# STM8S103.net
KiCad netlist of a schematic drawn in Altium Designer
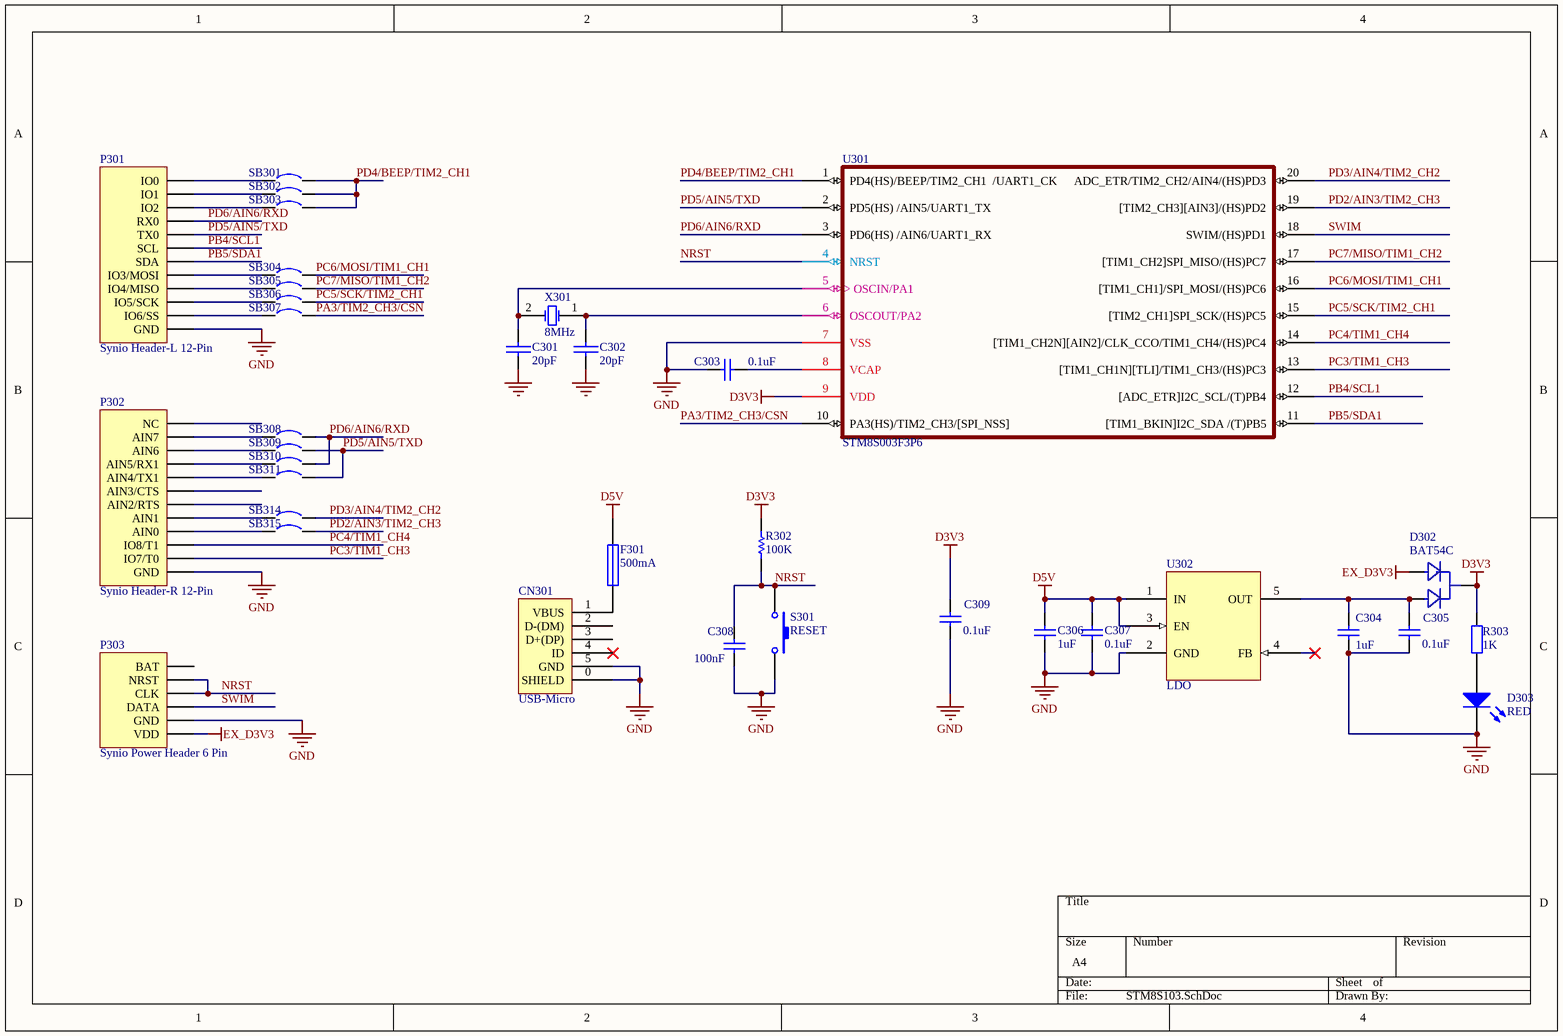
[diagram p0: STM8S103.SchDoc]

(export (version "E")
  (design (tool "Eeschema 10.0.6"))
  (components
    (comp (ref "C301")
      (value "20pF")
      (footprint "0603M")
      (description "Capacitor")
      (libsource (lib "*") (part "CAP"))
    )
    (comp (ref "C302")
      (value "20pF")
      (footprint "0603M")
      (description "Capacitor")
      (libsource (lib "*") (part "CAP"))
    )
    (comp (ref "C303")
      (value "0.1uF")
      (footprint "C0603L")
      (description "Capacitor")
      (libsource (lib "Misc") (part "Cap"))
    )
    (comp (ref "C304")
      (value "1uF")
      (footprint "0603M")
      (description "Capacitor")
      (libsource (lib "Studio") (part "Cap"))
    )
    (comp (ref "C305")
      (value "0.1uF")
      (footprint "0603M")
      (description "Capacitor")
      (libsource (lib "Studio") (part "Cap"))
    )
    (comp (ref "C306")
      (value "1uF")
      (footprint "C0603L")
      (description "Capacitor")
      (fields (field (name "Comment") "Cap") (field (name "PUBLISHER") "Altium Limited"))
      (libsource (lib "Miscellaneous Devices") (part "Cap"))
    )
    (comp (ref "C307")
      (value "0.1uF")
      (footprint "C0603L")
      (description "Capacitor")
      (fields (field (name "Comment") "Cap") (field (name "PUBLISHER") "Altium Limited"))
      (libsource (lib "Miscellaneous Devices") (part "Cap"))
    )
    (comp (ref "C308")
      (value "100nF")
      (footprint "0603M")
      (description "Capacitor")
      (fields (field (name "PUBLISHER") "Altium Limited"))
      (libsource (lib "Miscellaneous Devices") (part "CAP"))
    )
    (comp (ref "C309")
      (value "0.1uF")
      (footprint "0603M")
      (description "Capacitor")
      (libsource (lib "Studio") (part "Cap"))
    )
    (comp (ref "CN301")
      (value "USB-Micro")
      (footprint "USB-MICRO-Female-Lite")
      (libsource (lib "Connector") (part "USB-Micro"))
    )
    (comp (ref "D302")
      (value "BAT54C")
      (footprint "BAT54C")
      (description "DOUBLE SHOTTKEY DIODES")
      (libsource (lib "Misc") (part "BAT54C"))
    )
    (comp (ref "D303")
      (value "RED")
      (footprint "0603pn")
      (description "Typical INFRARED GaAs LED")
      (fields (field (name "PUBLISHER") "Altium Limited"))
      (libsource (lib "Miscellaneous Devices") (part "LED0"))
    )
    (comp (ref "F301")
      (value "500mA")
      (footprint "0805")
      (description "Fuse")
      (fields (field (name "PUBLISHER") "Altium Limited"))
      (libsource (lib "Studio") (part "Fuse 1"))
    )
    (comp (ref "P301")
      (value "Synio Header-L 12-Pin")
      (footprint "HDR1X12")
      (description "Synio Header-L, 12-Pin")
      (fields (field (name "PUBLISHER") "Altium Limited"))
      (libsource (lib "Connector") (part "Synio Header-L 12-Pin"))
    )
    (comp (ref "P302")
      (value "Synio Header-R 12-Pin")
      (footprint "HDR1X12")
      (description "Synio Header-R, 12-Pin")
      (fields (field (name "PUBLISHER") "Altium Limited"))
      (libsource (lib "Connector") (part "Synio Header-R 12-Pin"))
    )
    (comp (ref "P303")
      (value "Synio Power Header 6 Pin")
      (footprint "HDR1X6/2.54MM")
      (libsource (lib "Connector") (part "Synio Power Header 6 Pin"))
    )
    (comp (ref "R302")
      (value "100K")
      (footprint "0603M")
      (description "Resistor")
      (fields (field (name "PUBLISHER") "Altium Limited"))
      (libsource (lib "Miscellaneous Devices") (part "res1"))
    )
    (comp (ref "R303")
      (value "1K")
      (footprint "0603M")
      (description "Resistor")
      (fields (field (name "PUBLISHER") "Altium Limited"))
      (libsource (lib "Miscellaneous Devices") (part "Res2"))
    )
    (comp (ref "S301")
      (value "RESET")
      (footprint "KEY-2x4-SMD")
      (description "Switch")
      (fields (field (name "PUBLISHER") "Altium Limited"))
      (libsource (lib "Miscellaneous Devices") (part "SW-PB"))
    )
    (comp (ref "SB301")
      (value "Circuit Breaker")
      (footprint "JP2_SMD")
      (fields (field (name "PUBLISHER") "Altium Limited"))
      (libsource (lib "Misc") (part "Circuit Breaker"))
    )
    (comp (ref "SB302")
      (value "Circuit Breaker")
      (footprint "JP2_SMD")
      (fields (field (name "PUBLISHER") "Altium Limited"))
      (libsource (lib "Misc") (part "Circuit Breaker"))
    )
    (comp (ref "SB303")
      (value "Circuit Breaker")
      (footprint "JP2_SMD")
      (fields (field (name "PUBLISHER") "Altium Limited"))
      (libsource (lib "Misc") (part "Circuit Breaker"))
    )
    (comp (ref "SB304")
      (value "Circuit Breaker")
      (footprint "JP2_SMD")
      (fields (field (name "PUBLISHER") "Altium Limited"))
      (libsource (lib "Misc") (part "Circuit Breaker"))
    )
    (comp (ref "SB305")
      (value "Circuit Breaker")
      (footprint "JP2_SMD")
      (fields (field (name "PUBLISHER") "Altium Limited"))
      (libsource (lib "Misc") (part "Circuit Breaker"))
    )
    (comp (ref "SB306")
      (value "Circuit Breaker")
      (footprint "JP2_SMD")
      (fields (field (name "PUBLISHER") "Altium Limited"))
      (libsource (lib "Misc") (part "Circuit Breaker"))
    )
    (comp (ref "SB307")
      (value "Circuit Breaker")
      (footprint "JP2_SMD")
      (fields (field (name "PUBLISHER") "Altium Limited"))
      (libsource (lib "Misc") (part "Circuit Breaker"))
    )
    (comp (ref "SB308")
      (value "Circuit Breaker")
      (footprint "JP2_SMD")
      (fields (field (name "PUBLISHER") "Altium Limited"))
      (libsource (lib "Misc") (part "Circuit Breaker"))
    )
    (comp (ref "SB309")
      (value "Circuit Breaker")
      (footprint "JP2_SMD")
      (fields (field (name "PUBLISHER") "Altium Limited"))
      (libsource (lib "Misc") (part "Circuit Breaker"))
    )
    (comp (ref "SB310")
      (value "Circuit Breaker")
      (footprint "JP2_SMD")
      (fields (field (name "PUBLISHER") "Altium Limited"))
      (libsource (lib "Misc") (part "Circuit Breaker"))
    )
    (comp (ref "SB311")
      (value "Circuit Breaker")
      (footprint "JP2_SMD")
      (fields (field (name "PUBLISHER") "Altium Limited"))
      (libsource (lib "Misc") (part "Circuit Breaker"))
    )
    (comp (ref "SB314")
      (value "Circuit Breaker")
      (footprint "JP2_SMD")
      (fields (field (name "PUBLISHER") "Altium Limited"))
      (libsource (lib "Misc") (part "Circuit Breaker"))
    )
    (comp (ref "SB315")
      (value "Circuit Breaker")
      (footprint "JP2_SMD")
      (fields (field (name "PUBLISHER") "Altium Limited"))
      (libsource (lib "Misc") (part "Circuit Breaker"))
    )
    (comp (ref "U301")
      (value "STM8S003F3P6")
      (footprint "TSSOP20")
      (description "ST 8-bit  Microcontroller")
      (libsource (lib "Microcontroller Unit") (part "STM8S103F2P6"))
    )
    (comp (ref "U302")
      (value "LDO")
      (footprint "SOT23-5")
      (description "General LDO SOT23-5")
      (libsource (lib "Power") (part "LDO-SOT23-5"))
    )
    (comp (ref "X301")
      (value "8MHz")
      (footprint "XTAL_49S")
      (description "Crystal Oscillator")
      (fields (field (name "PUBLISHER") "Altium Limited"))
      (libsource (lib "MCD_TOOLS") (part "XTAL"))
    )
  )
  (nets
    (net (code "1") (name "/NRST") (class "Default")
      (node (ref "C308") (pin "2") (pinfunction "2_2") (pintype "passive"))
      (node (ref "P303") (pin "4") (pinfunction "CLK_4") (pintype "passive"))
      (node (ref "P303") (pin "5") (pinfunction "NRST_5") (pintype "passive"))
      (node (ref "R302") (pin "1") (pinfunction "1_1") (pintype "passive"))
      (node (ref "S301") (pin "2") (pinfunction "2_2") (pintype "passive"))
      (node (ref "U301") (pin "4") (pinfunction "NRST_4") (pintype "bidirectional"))
    )
    (net (code "2") (name "/PA3{slash}TIM2_CH3{slash}CSN") (class "Default")
      (node (ref "SB307") (pin "2") (pinfunction "2_2") (pintype "passive"))
      (node (ref "U301") (pin "10") (pinfunction "PA3(HS)/TIM2_CH3/[SPI_NSS]_10") (pintype "bidirectional"))
    )
    (net (code "3") (name "/PB4{slash}SCL1") (class "Default")
      (node (ref "P301") (pin "7") (pinfunction "SCL_7") (pintype "passive"))
      (node (ref "U301") (pin "12") (pinfunction "[ADC_ETR]I2C_SCL/(T)PB4_12") (pintype "bidirectional"))
    )
    (net (code "4") (name "/PB5{slash}SDA1") (class "Default")
      (node (ref "P301") (pin "6") (pinfunction "SDA_6") (pintype "passive"))
      (node (ref "U301") (pin "11") (pinfunction "[TIM1_BKIN]I2C_SDA_/(T)PB5_11") (pintype "bidirectional"))
    )
    (net (code "5") (name "/PC3{slash}TIM1_CH3") (class "Default")
      (node (ref "P302") (pin "2") (pinfunction "IO7/T0_2") (pintype "passive"))
      (node (ref "U301") (pin "13") (pinfunction "[TIM1_CH1N][TLI]/TIM1_CH3/(HS)PC3_13") (pintype "bidirectional"))
    )
    (net (code "6") (name "/PC4{slash}TIM1_CH4") (class "Default")
      (node (ref "P302") (pin "3") (pinfunction "IO8/T1_3") (pintype "passive"))
      (node (ref "U301") (pin "14") (pinfunction "[TIM1_CH2N][AIN2]/CLK_CCO/TIM1_CH4/(HS)PC4_14") (pintype "bidirectional"))
    )
    (net (code "7") (name "/PC5{slash}SCK{slash}TIM2_CH1") (class "Default")
      (node (ref "SB306") (pin "2") (pinfunction "2_2") (pintype "passive"))
      (node (ref "U301") (pin "15") (pinfunction "[TIM2_CH1]SPI_SCK/(HS)PC5_15") (pintype "bidirectional"))
    )
    (net (code "8") (name "/PC6{slash}MOSI{slash}TIM1_CH1") (class "Default")
      (node (ref "SB304") (pin "2") (pinfunction "2_2") (pintype "passive"))
      (node (ref "U301") (pin "16") (pinfunction "[TIM1_CH1]/SPI_MOSI/(HS)PC6_16") (pintype "bidirectional"))
    )
    (net (code "9") (name "/PC7{slash}MISO{slash}TIM1_CH2") (class "Default")
      (node (ref "SB305") (pin "2") (pinfunction "2_2") (pintype "passive"))
      (node (ref "U301") (pin "17") (pinfunction "[TIM1_CH2]SPI_MISO/(HS)PC7_17") (pintype "bidirectional"))
    )
    (net (code "10") (name "/PD2{slash}AIN3{slash}TIM2_CH3") (class "Default")
      (node (ref "SB315") (pin "2") (pinfunction "2_2") (pintype "passive"))
      (node (ref "U301") (pin "19") (pinfunction "[TIM2_CH3][AIN3]/(HS)PD2_19") (pintype "bidirectional"))
    )
    (net (code "11") (name "/PD3{slash}AIN4{slash}TIM2_CH2") (class "Default")
      (node (ref "SB314") (pin "2") (pinfunction "2_2") (pintype "passive"))
      (node (ref "U301") (pin "20") (pinfunction "ADC_ETR/TIM2_CH2/AIN4/(HS)PD3_20") (pintype "bidirectional"))
    )
    (net (code "12") (name "/PD4{slash}BEEP{slash}TIM2_CH1") (class "Default")
      (node (ref "SB301") (pin "2") (pinfunction "2_2") (pintype "passive"))
      (node (ref "SB302") (pin "2") (pinfunction "2_2") (pintype "passive"))
      (node (ref "SB303") (pin "2") (pinfunction "2_2") (pintype "passive"))
      (node (ref "U301") (pin "1") (pinfunction "PD4(HS)/BEEP/TIM2_CH1__/UART1_CK_1") (pintype "bidirectional"))
    )
    (net (code "13") (name "/PD5{slash}AIN5{slash}TXD") (class "Default")
      (node (ref "P301") (pin "8") (pinfunction "TX0_8") (pintype "passive"))
      (node (ref "SB309") (pin "2") (pinfunction "2_2") (pintype "passive"))
      (node (ref "SB311") (pin "2") (pinfunction "2_2") (pintype "passive"))
      (node (ref "U301") (pin "2") (pinfunction "PD5(HS)_/AIN5/UART1_TX_2") (pintype "bidirectional"))
    )
    (net (code "14") (name "/PD6{slash}AIN6{slash}RXD") (class "Default")
      (node (ref "P301") (pin "9") (pinfunction "RX0_9") (pintype "passive"))
      (node (ref "SB308") (pin "2") (pinfunction "2_2") (pintype "passive"))
      (node (ref "SB310") (pin "2") (pinfunction "2_2") (pintype "passive"))
      (node (ref "U301") (pin "3") (pinfunction "PD6(HS)_/AIN6/UART1_RX_3") (pintype "bidirectional"))
    )
    (net (code "15") (name "/SWIM") (class "Default")
      (node (ref "P303") (pin "3") (pinfunction "DATA_3") (pintype "passive"))
      (node (ref "U301") (pin "18") (pinfunction "SWIM/(HS)PD1_18") (pintype "bidirectional"))
    )
    (net (code "16") (name "D3V3") (class "Default")
      (node (ref "C309") (pin "2") (pinfunction "2_2") (pintype "passive"))
      (node (ref "D302") (pin "3") (pinfunction "3_3") (pintype "passive"))
      (node (ref "R302") (pin "2") (pinfunction "2_2") (pintype "passive"))
      (node (ref "R303") (pin "2") (pinfunction "2_2") (pintype "passive"))
      (node (ref "U301") (pin "9") (pinfunction "VDD_9") (pintype "power_in"))
    )
    (net (code "17") (name "D5V") (class "Default")
      (node (ref "C306") (pin "2") (pinfunction "2_2") (pintype "passive"))
      (node (ref "C307") (pin "2") (pinfunction "2_2") (pintype "passive"))
      (node (ref "F301") (pin "1") (pinfunction "1_1") (pintype "passive"))
      (node (ref "U302") (pin "1") (pinfunction "IN_1") (pintype "power_in"))
      (node (ref "U302") (pin "3") (pinfunction "EN_3") (pintype "input"))
    )
    (net (code "18") (name "EX_D3V3") (class "Default")
      (node (ref "D302") (pin "1") (pintype "passive"))
      (node (ref "P303") (pin "1") (pinfunction "VDD_1") (pintype "passive"))
    )
    (net (code "19") (name "GND") (class "Default")
      (node (ref "C301") (pin "2") (pinfunction "2_2") (pintype "passive"))
      (node (ref "C302") (pin "2") (pinfunction "2_2") (pintype "passive"))
      (node (ref "C303") (pin "2") (pinfunction "2_2") (pintype "passive"))
      (node (ref "C304") (pin "1") (pinfunction "1_1") (pintype "passive"))
      (node (ref "C305") (pin "1") (pinfunction "1_1") (pintype "passive"))
      (node (ref "C306") (pin "1") (pinfunction "1_1") (pintype "passive"))
      (node (ref "C307") (pin "1") (pinfunction "1_1") (pintype "passive"))
      (node (ref "C308") (pin "1") (pinfunction "1_1") (pintype "passive"))
      (node (ref "C309") (pin "1") (pinfunction "1_1") (pintype "passive"))
      (node (ref "CN301") (pin "0") (pinfunction "SHIELD_0") (pintype "passive"))
      (node (ref "CN301") (pin "5") (pinfunction "GND_5") (pintype "passive"))
      (node (ref "D303") (pin "2") (pinfunction "K_2") (pintype "passive"))
      (node (ref "P301") (pin "1") (pinfunction "GND_1") (pintype "passive"))
      (node (ref "P302") (pin "1") (pinfunction "GND_1") (pintype "passive"))
      (node (ref "P303") (pin "2") (pinfunction "GND_2") (pintype "passive"))
      (node (ref "S301") (pin "1") (pinfunction "1_1") (pintype "passive"))
      (node (ref "U301") (pin "7") (pinfunction "VSS_7") (pintype "power_in"))
      (node (ref "U302") (pin "2") (pinfunction "GND_2") (pintype "power_in"))
    )
    (net (code "20") (name "Net-(CN301-VBUS)") (class "Default")
      (node (ref "CN301") (pin "1") (pinfunction "VBUS_1") (pintype "passive"))
      (node (ref "F301") (pin "2") (pinfunction "2_2") (pintype "passive"))
    )
    (net (code "21") (name "Net-(D303-A)") (class "Default")
      (node (ref "D303") (pin "1") (pinfunction "A_1") (pintype "passive"))
      (node (ref "R303") (pin "1") (pinfunction "1_1") (pintype "passive"))
    )
    (net (code "22") (name "Net-(P301-IO0)") (class "Default")
      (node (ref "P301") (pin "12") (pinfunction "IO0_12") (pintype "passive"))
      (node (ref "SB301") (pin "1") (pinfunction "1_1") (pintype "passive"))
    )
    (net (code "23") (name "Net-(P301-IO1)") (class "Default")
      (node (ref "P301") (pin "11") (pinfunction "IO1_11") (pintype "passive"))
      (node (ref "SB302") (pin "1") (pinfunction "1_1") (pintype "passive"))
    )
    (net (code "24") (name "Net-(P301-IO2)") (class "Default")
      (node (ref "P301") (pin "10") (pinfunction "IO2_10") (pintype "passive"))
      (node (ref "SB303") (pin "1") (pinfunction "1_1") (pintype "passive"))
    )
    (net (code "25") (name "Net-(P301-IO3{slash}MOSI)") (class "Default")
      (node (ref "P301") (pin "5") (pinfunction "IO3/MOSI_5") (pintype "passive"))
      (node (ref "SB304") (pin "1") (pinfunction "1_1") (pintype "passive"))
    )
    (net (code "26") (name "Net-(P301-IO4{slash}MISO)") (class "Default")
      (node (ref "P301") (pin "4") (pinfunction "IO4/MISO_4") (pintype "passive"))
      (node (ref "SB305") (pin "1") (pinfunction "1_1") (pintype "passive"))
    )
    (net (code "27") (name "Net-(P301-IO5{slash}SCK)") (class "Default")
      (node (ref "P301") (pin "3") (pinfunction "IO5/SCK_3") (pintype "passive"))
      (node (ref "SB306") (pin "1") (pinfunction "1_1") (pintype "passive"))
    )
    (net (code "28") (name "Net-(P301-IO6{slash}SS)") (class "Default")
      (node (ref "P301") (pin "2") (pinfunction "IO6/SS_2") (pintype "passive"))
      (node (ref "SB307") (pin "1") (pinfunction "1_1") (pintype "passive"))
    )
    (net (code "29") (name "Net-(P302-AIN0)") (class "Default")
      (node (ref "P302") (pin "4") (pinfunction "AIN0_4") (pintype "passive"))
      (node (ref "SB315") (pin "1") (pinfunction "1_1") (pintype "passive"))
    )
    (net (code "30") (name "Net-(P302-AIN1)") (class "Default")
      (node (ref "P302") (pin "5") (pinfunction "AIN1_5") (pintype "passive"))
      (node (ref "SB314") (pin "1") (pinfunction "1_1") (pintype "passive"))
    )
    (net (code "31") (name "Net-(P302-AIN4{slash}TX1)") (class "Default")
      (node (ref "P302") (pin "8") (pinfunction "AIN4/TX1_8") (pintype "passive"))
      (node (ref "SB311") (pin "1") (pinfunction "1_1") (pintype "passive"))
    )
    (net (code "32") (name "Net-(P302-AIN5{slash}RX1)") (class "Default")
      (node (ref "P302") (pin "9") (pinfunction "AIN5/RX1_9") (pintype "passive"))
      (node (ref "SB310") (pin "1") (pinfunction "1_1") (pintype "passive"))
    )
    (net (code "33") (name "Net-(P302-AIN6)") (class "Default")
      (node (ref "P302") (pin "10") (pinfunction "AIN6_10") (pintype "passive"))
      (node (ref "SB309") (pin "1") (pinfunction "1_1") (pintype "passive"))
    )
    (net (code "34") (name "Net-(P302-AIN7)") (class "Default")
      (node (ref "P302") (pin "11") (pinfunction "AIN7_11") (pintype "passive"))
      (node (ref "SB308") (pin "1") (pinfunction "1_1") (pintype "passive"))
    )
    (net (code "35") (name "Net-(U301-OSCIN{slash}PA1)") (class "Default")
      (node (ref "C301") (pin "1") (pinfunction "1_1") (pintype "passive"))
      (node (ref "U301") (pin "5") (pinfunction "OSCIN/PA1_5") (pintype "bidirectional"))
      (node (ref "X301") (pin "2") (pinfunction "OSC2_2") (pintype "passive"))
    )
    (net (code "36") (name "Net-(U301-OSCOUT{slash}PA2)") (class "Default")
      (node (ref "C302") (pin "1") (pinfunction "1_1") (pintype "passive"))
      (node (ref "U301") (pin "6") (pinfunction "OSCOUT/PA2_6") (pintype "bidirectional"))
      (node (ref "X301") (pin "1") (pinfunction "OSC1_1") (pintype "passive"))
    )
    (net (code "37") (name "Net-(U301-VCAP)") (class "Default")
      (node (ref "C303") (pin "1") (pinfunction "1_1") (pintype "passive"))
      (node (ref "U301") (pin "8") (pinfunction "VCAP_8") (pintype "power_in"))
    )
    (net (code "38") (name "Net-(U302-OUT)") (class "Default")
      (node (ref "C304") (pin "2") (pinfunction "2_2") (pintype "passive"))
      (node (ref "C305") (pin "2") (pinfunction "2_2") (pintype "passive"))
      (node (ref "D302") (pin "2") (pintype "passive"))
      (node (ref "U302") (pin "5") (pinfunction "OUT_5") (pintype "power_in"))
    )
    (net (code "39") (name "unconnected-(CN301-D+(DP)-Pad3)") (class "Default")
      (node (ref "CN301") (pin "3") (pinfunction "D+(DP)_3") (pintype "passive"))
    )
    (net (code "40") (name "unconnected-(CN301-D-(DM)-Pad2)") (class "Default")
      (node (ref "CN301") (pin "2") (pinfunction "D-(DM)_2") (pintype "passive"))
    )
    (net (code "41") (name "unconnected-(CN301-ID-Pad4)") (class "Default")
      (node (ref "CN301") (pin "4") (pinfunction "ID_4") (pintype "passive+no_connect"))
    )
    (net (code "42") (name "unconnected-(P302-AIN2{slash}RTS-Pad6)") (class "Default")
      (node (ref "P302") (pin "6") (pinfunction "AIN2/RTS_6") (pintype "passive"))
    )
    (net (code "43") (name "unconnected-(P302-AIN3{slash}CTS-Pad7)") (class "Default")
      (node (ref "P302") (pin "7") (pinfunction "AIN3/CTS_7") (pintype "passive"))
    )
    (net (code "44") (name "unconnected-(P302-NC-Pad12)") (class "Default")
      (node (ref "P302") (pin "12") (pinfunction "NC_12") (pintype "passive"))
    )
    (net (code "45") (name "unconnected-(P303-BAT-Pad6)") (class "Default")
      (node (ref "P303") (pin "6") (pinfunction "BAT_6") (pintype "passive"))
    )
    (net (code "46") (name "unconnected-(U302-FB-Pad4)") (class "Default")
      (node (ref "U302") (pin "4") (pinfunction "FB_4") (pintype "input+no_connect"))
    )
  )
)
